# untitled.net
KiCad netlist of a schematic drawn in EAGLE
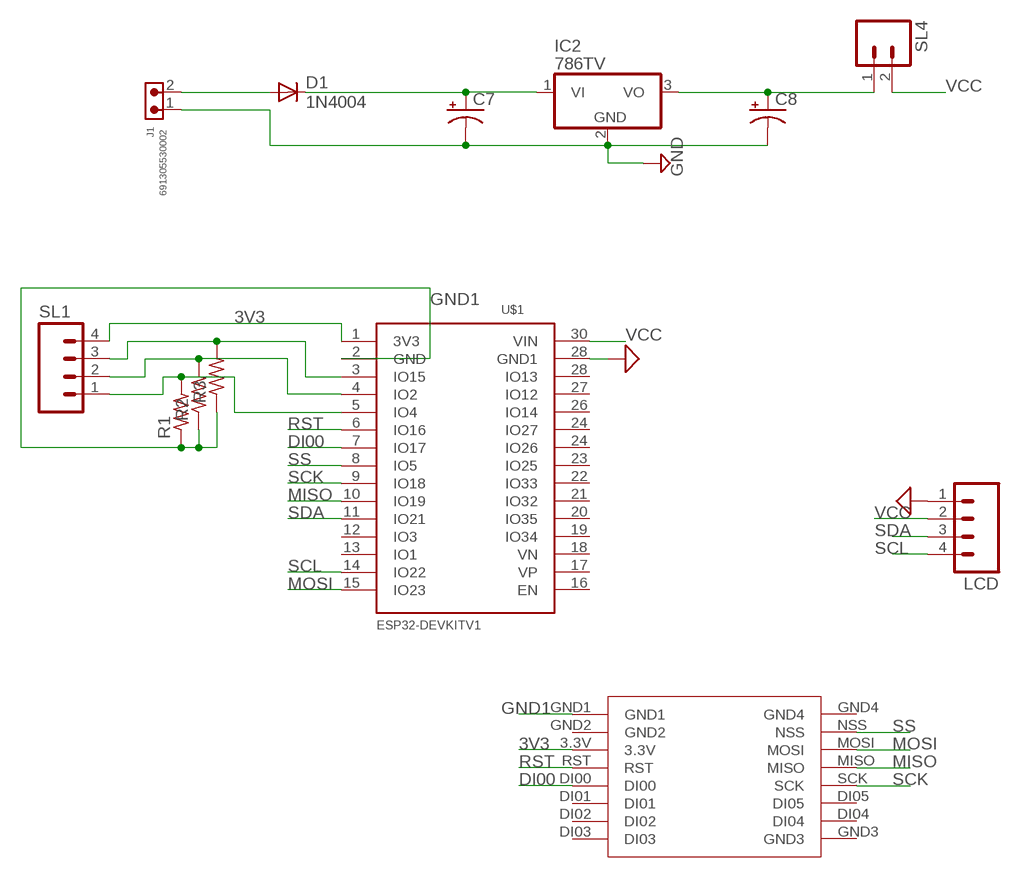
[diagram p0: schematic, sheet 1]

(export (version "E")
  (design (tool "Eeschema 10.0.6"))
  (components
    (comp (ref "C7")
      (value "CAPACITOR-PE5-10.5")
      (footprint "eagle-import:E5-10,5")
      (libsource (lib "eagle-import") (part "CAPACITOR-PE5-10.5"))
    )
    (comp (ref "C8")
      (value "CAPACITOR-PE5-6")
      (footprint "eagle-import:E5-6")
      (libsource (lib "eagle-import") (part "CAPACITOR-PE5-6"))
    )
    (comp (ref "D1")
      (value "1N4004")
      (footprint "eagle-import:DO41-10")
      (libsource (lib "eagle-import") (part "1N4004"))
    )
    (comp (ref "IC2")
      (value "786TV")
      (footprint "eagle-import:TO220V")
      (libsource (lib "eagle-import") (part "78TV6"))
    )
    (comp (ref "J1")
      (value "691305530002")
      (footprint "eagle-import:691305530002")
      (libsource (lib "eagle-import") (part "691305530002"))
    )
    (comp (ref "LCD")
      (value "M04")
      (footprint "eagle-import:04P")
      (libsource (lib "eagle-import") (part "M04"))
    )
    (comp (ref "R1")
      (value "R-US_0207/10")
      (footprint "eagle-import:0207_10")
      (libsource (lib "eagle-import") (part "R-US_0207/10"))
    )
    (comp (ref "R2")
      (value "R-US_0207/10")
      (footprint "eagle-import:0207_10")
      (libsource (lib "eagle-import") (part "R-US_0207/10"))
    )
    (comp (ref "R3")
      (value "R-US_0207/7")
      (footprint "eagle-import:0207_7")
      (libsource (lib "eagle-import") (part "R-US_0207/7"))
    )
    (comp (ref "SL1")
      (value "M04")
      (footprint "eagle-import:04P")
      (libsource (lib "eagle-import") (part "M04"))
    )
    (comp (ref "SL4")
      (value "M02")
      (footprint "eagle-import:02P")
      (libsource (lib "eagle-import") (part "M02"))
    )
    (comp (ref "U$1")
      (value "ESP32DEVKITV1")
      (footprint "eagle-import:ESP32-DEVKITV1")
      (libsource (lib "eagle-import") (part "ESP32DEVKITV1"))
    )
    (comp (ref "U$2")
      (value "LORASX1278")
      (footprint "eagle-import:LORASX1278")
      (libsource (lib "eagle-import") (part "LORASX1278"))
    )
  )
  (nets
    (net (code "1") (name "/3V3") (class "Default")
      (node (ref "SL1") (pin "4") (pinfunction "4_4") (pintype "passive"))
      (node (ref "U$1") (pin "1") (pinfunction "3V3_1") (pintype "bidirectional"))
      (node (ref "U$2") (pin "3.3V") (pinfunction "3.3V_3.3V") (pintype "bidirectional"))
    )
    (net (code "2") (name "/DI00") (class "Default")
      (node (ref "U$1") (pin "7") (pinfunction "IO17_7") (pintype "bidirectional"))
      (node (ref "U$2") (pin "DI00") (pinfunction "DI00_DI00") (pintype "bidirectional"))
    )
    (net (code "3") (name "/GND1") (class "Default")
      (node (ref "R1") (pin "1") (pinfunction "1_1") (pintype "passive"))
      (node (ref "R2") (pin "1") (pinfunction "1_1") (pintype "passive"))
      (node (ref "R3") (pin "1") (pinfunction "1_1") (pintype "passive"))
      (node (ref "U$1") (pin "2") (pinfunction "GND_2") (pintype "bidirectional"))
      (node (ref "U$2") (pin "GND1") (pinfunction "GND1_GND1") (pintype "bidirectional"))
    )
    (net (code "4") (name "/MISO") (class "Default")
      (node (ref "U$1") (pin "10") (pinfunction "IO19_10") (pintype "bidirectional"))
      (node (ref "U$2") (pin "MISO") (pinfunction "MISO_MISO") (pintype "bidirectional"))
    )
    (net (code "5") (name "/MOSI") (class "Default")
      (node (ref "U$1") (pin "15") (pinfunction "IO23_15") (pintype "bidirectional"))
      (node (ref "U$2") (pin "MOSI") (pinfunction "MOSI_MOSI") (pintype "bidirectional"))
    )
    (net (code "6") (name "/RST") (class "Default")
      (node (ref "U$1") (pin "6") (pinfunction "IO16_6") (pintype "bidirectional"))
      (node (ref "U$2") (pin "RST") (pinfunction "RST_RST") (pintype "bidirectional"))
    )
    (net (code "7") (name "/SCK") (class "Default")
      (node (ref "U$1") (pin "9") (pinfunction "IO18_9") (pintype "bidirectional"))
      (node (ref "U$2") (pin "SCK") (pinfunction "SCK_SCK") (pintype "bidirectional"))
    )
    (net (code "8") (name "/SCL") (class "Default")
      (node (ref "LCD") (pin "4") (pinfunction "4_4") (pintype "passive"))
      (node (ref "U$1") (pin "14") (pinfunction "IO22_14") (pintype "bidirectional"))
    )
    (net (code "9") (name "/SDA") (class "Default")
      (node (ref "LCD") (pin "3") (pinfunction "3_3") (pintype "passive"))
      (node (ref "U$1") (pin "11") (pinfunction "IO21_11") (pintype "bidirectional"))
    )
    (net (code "10") (name "/SS") (class "Default")
      (node (ref "U$1") (pin "8") (pinfunction "IO5_8") (pintype "bidirectional"))
      (node (ref "U$2") (pin "NSS") (pinfunction "NSS_NSS") (pintype "bidirectional"))
    )
    (net (code "11") (name "/VCC") (class "Default")
      (node (ref "LCD") (pin "2") (pinfunction "2_2") (pintype "passive"))
      (node (ref "SL4") (pin "2") (pinfunction "2_2") (pintype "passive"))
      (node (ref "U$1") (pin "30") (pinfunction "VIN_30") (pintype "bidirectional"))
    )
    (net (code "12") (name "GND") (class "Default")
      (node (ref "C7") (pin "-") (pinfunction "-_-") (pintype "passive"))
      (node (ref "C8") (pin "-") (pinfunction "-_-") (pintype "passive"))
      (node (ref "IC2") (pin "2") (pinfunction "GND_2") (pintype "passive"))
      (node (ref "J1") (pin "1") (pinfunction "1_1") (pintype "passive"))
      (node (ref "LCD") (pin "1") (pinfunction "1_1") (pintype "passive"))
      (node (ref "U$1") (pin "28") (pinfunction "GND1_28") (pintype "bidirectional"))
    )
    (net (code "13") (name "Net-(D1-PadA)") (class "Default")
      (node (ref "D1") (pin "A") (pinfunction "A_A") (pintype "passive"))
      (node (ref "J1") (pin "2") (pinfunction "2_2") (pintype "passive"))
    )
    (net (code "14") (name "Net-(IC2-VI)") (class "Default")
      (node (ref "C7") (pin "+") (pinfunction "+_+") (pintype "passive"))
      (node (ref "D1") (pin "C") (pinfunction "C_C") (pintype "passive"))
      (node (ref "IC2") (pin "1") (pinfunction "VI_1") (pintype "input"))
    )
    (net (code "15") (name "Net-(IC2-VO)") (class "Default")
      (node (ref "C8") (pin "+") (pinfunction "+_+") (pintype "passive"))
      (node (ref "IC2") (pin "3") (pinfunction "VO_3") (pintype "passive"))
      (node (ref "SL4") (pin "1") (pinfunction "1_1") (pintype "passive"))
    )
    (net (code "16") (name "Net-(U$1-IO2)") (class "Default")
      (node (ref "R2") (pin "2") (pinfunction "2_2") (pintype "passive"))
      (node (ref "SL1") (pin "2") (pinfunction "2_2") (pintype "passive"))
      (node (ref "U$1") (pin "4") (pinfunction "IO2_4") (pintype "bidirectional"))
    )
    (net (code "17") (name "Net-(U$1-IO4)") (class "Default")
      (node (ref "R1") (pin "2") (pinfunction "2_2") (pintype "passive"))
      (node (ref "SL1") (pin "1") (pinfunction "1_1") (pintype "passive"))
      (node (ref "U$1") (pin "5") (pinfunction "IO4_5") (pintype "bidirectional"))
    )
    (net (code "18") (name "Net-(U$1-IO15)") (class "Default")
      (node (ref "R3") (pin "2") (pinfunction "2_2") (pintype "passive"))
      (node (ref "SL1") (pin "3") (pinfunction "3_3") (pintype "passive"))
      (node (ref "U$1") (pin "3") (pinfunction "IO15_3") (pintype "bidirectional"))
    )
    (net (code "19") (name "unconnected-(U$1-EN-Pad16)") (class "Default")
      (node (ref "U$1") (pin "16") (pinfunction "EN_16") (pintype "bidirectional"))
    )
    (net (code "20") (name "unconnected-(U$1-IO1-Pad13)") (class "Default")
      (node (ref "U$1") (pin "13") (pinfunction "IO1_13") (pintype "bidirectional"))
    )
    (net (code "21") (name "unconnected-(U$1-IO3-Pad12)") (class "Default")
      (node (ref "U$1") (pin "12") (pinfunction "IO3_12") (pintype "bidirectional"))
    )
    (net (code "22") (name "unconnected-(U$1-IO12-Pad27)") (class "Default")
      (node (ref "U$1") (pin "27") (pinfunction "IO12_27") (pintype "bidirectional"))
    )
    (net (code "23") (name "unconnected-(U$1-IO13-Pad28)") (class "Default")
      (node (ref "U$1") (pin "28") (pinfunction "IO13_28") (pintype "bidirectional"))
    )
    (net (code "24") (name "unconnected-(U$1-IO14-Pad26)") (class "Default")
      (node (ref "U$1") (pin "26") (pinfunction "IO14_26") (pintype "bidirectional"))
    )
    (net (code "25") (name "unconnected-(U$1-IO25-Pad23)") (class "Default")
      (node (ref "U$1") (pin "23") (pinfunction "IO25_23") (pintype "bidirectional"))
    )
    (net (code "26") (name "unconnected-(U$1-IO26-Pad24)") (class "Default")
      (node (ref "U$1") (pin "24") (pinfunction "IO26_24") (pintype "bidirectional"))
    )
    (net (code "27") (name "unconnected-(U$1-IO27-Pad24)") (class "Default")
      (node (ref "U$1") (pin "24") (pinfunction "IO27_24") (pintype "bidirectional"))
    )
    (net (code "28") (name "unconnected-(U$1-IO32-Pad21)") (class "Default")
      (node (ref "U$1") (pin "21") (pinfunction "IO32_21") (pintype "bidirectional"))
    )
    (net (code "29") (name "unconnected-(U$1-IO33-Pad22)") (class "Default")
      (node (ref "U$1") (pin "22") (pinfunction "IO33_22") (pintype "bidirectional"))
    )
    (net (code "30") (name "unconnected-(U$1-IO34-Pad19)") (class "Default")
      (node (ref "U$1") (pin "19") (pinfunction "IO34_19") (pintype "bidirectional"))
    )
    (net (code "31") (name "unconnected-(U$1-IO35-Pad20)") (class "Default")
      (node (ref "U$1") (pin "20") (pinfunction "IO35_20") (pintype "bidirectional"))
    )
    (net (code "32") (name "unconnected-(U$1-VN-Pad18)") (class "Default")
      (node (ref "U$1") (pin "18") (pinfunction "VN_18") (pintype "bidirectional"))
    )
    (net (code "33") (name "unconnected-(U$1-VP-Pad17)") (class "Default")
      (node (ref "U$1") (pin "17") (pinfunction "VP_17") (pintype "bidirectional"))
    )
    (net (code "34") (name "unconnected-(U$2-PadDI01)") (class "Default")
      (node (ref "U$2") (pin "DI01") (pinfunction "DI01_DI01") (pintype "bidirectional"))
    )
    (net (code "35") (name "unconnected-(U$2-PadDI02)") (class "Default")
      (node (ref "U$2") (pin "DI02") (pinfunction "DI02_DI02") (pintype "bidirectional"))
    )
    (net (code "36") (name "unconnected-(U$2-PadDI03)") (class "Default")
      (node (ref "U$2") (pin "DI03") (pinfunction "DI03_DI03") (pintype "bidirectional"))
    )
    (net (code "37") (name "unconnected-(U$2-PadDI04)") (class "Default")
      (node (ref "U$2") (pin "DI04") (pinfunction "DI04_DI04") (pintype "bidirectional"))
    )
    (net (code "38") (name "unconnected-(U$2-PadDI05)") (class "Default")
      (node (ref "U$2") (pin "DI05") (pinfunction "DI05_DI05") (pintype "bidirectional"))
    )
    (net (code "39") (name "unconnected-(U$2-PadGND2)") (class "Default")
      (node (ref "U$2") (pin "GND2") (pinfunction "GND2_GND2") (pintype "bidirectional"))
    )
    (net (code "40") (name "unconnected-(U$2-PadGND3)") (class "Default")
      (node (ref "U$2") (pin "GND3") (pinfunction "GND3_GND3") (pintype "bidirectional"))
    )
    (net (code "41") (name "unconnected-(U$2-PadGND4)") (class "Default")
      (node (ref "U$2") (pin "GND4") (pinfunction "GND4_GND4") (pintype "bidirectional"))
    )
  )
)
